# schmitt_trigger.net
KiCad netlist of a schematic drawn in EAGLE
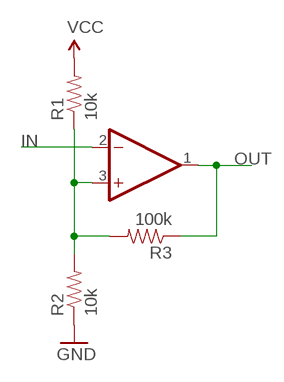
[diagram p0: schematic, sheet 1]

(export (version "E")
  (design (tool "Eeschema 10.0.6"))
  (components
    (comp (ref "IC1")
      (value "MCP6022")
      (footprint "eagle-import:SOIC8_150MIL")
      (libsource (lib "eagle-import") (part "MCP6022"))
    )
    (comp (ref "R1")
      (value "10k")
      (footprint "eagle-import:0402-RES")
      (libsource (lib "eagle-import") (part "RESISTOR0402-RES"))
    )
    (comp (ref "R2")
      (value "10k")
      (footprint "eagle-import:0402-RES")
      (libsource (lib "eagle-import") (part "RESISTOR0402-RES"))
    )
    (comp (ref "R3")
      (value "100k")
      (footprint "eagle-import:0402-RES")
      (libsource (lib "eagle-import") (part "RESISTOR0402-RES"))
    )
  )
  (nets
    (net (code "1") (name "/IN") (class "Default")
      (node (ref "IC1") (pin "2") (pinfunction "-IN_2") (pintype "input"))
    )
    (net (code "2") (name "/OUT") (class "Default")
      (node (ref "IC1") (pin "1") (pinfunction "OUT_1") (pintype "output"))
      (node (ref "R3") (pin "1") (pinfunction "1_1") (pintype "passive"))
    )
    (net (code "3") (name "GND") (class "Default")
      (node (ref "R2") (pin "1") (pinfunction "1_1") (pintype "passive"))
    )
    (net (code "4") (name "Net-(IC1A-+IN)") (class "Default")
      (node (ref "IC1") (pin "3") (pinfunction "+IN_3") (pintype "input"))
      (node (ref "R1") (pin "1") (pinfunction "1_1") (pintype "passive"))
      (node (ref "R2") (pin "2") (pinfunction "2_2") (pintype "passive"))
      (node (ref "R3") (pin "2") (pinfunction "2_2") (pintype "passive"))
    )
    (net (code "5") (name "VCC") (class "Default")
      (node (ref "R1") (pin "2") (pinfunction "2_2") (pintype "passive"))
    )
  )
)
